# OMODRI_EtherCAT_0.net
KiCad netlist of a schematic drawn in Altium Designer
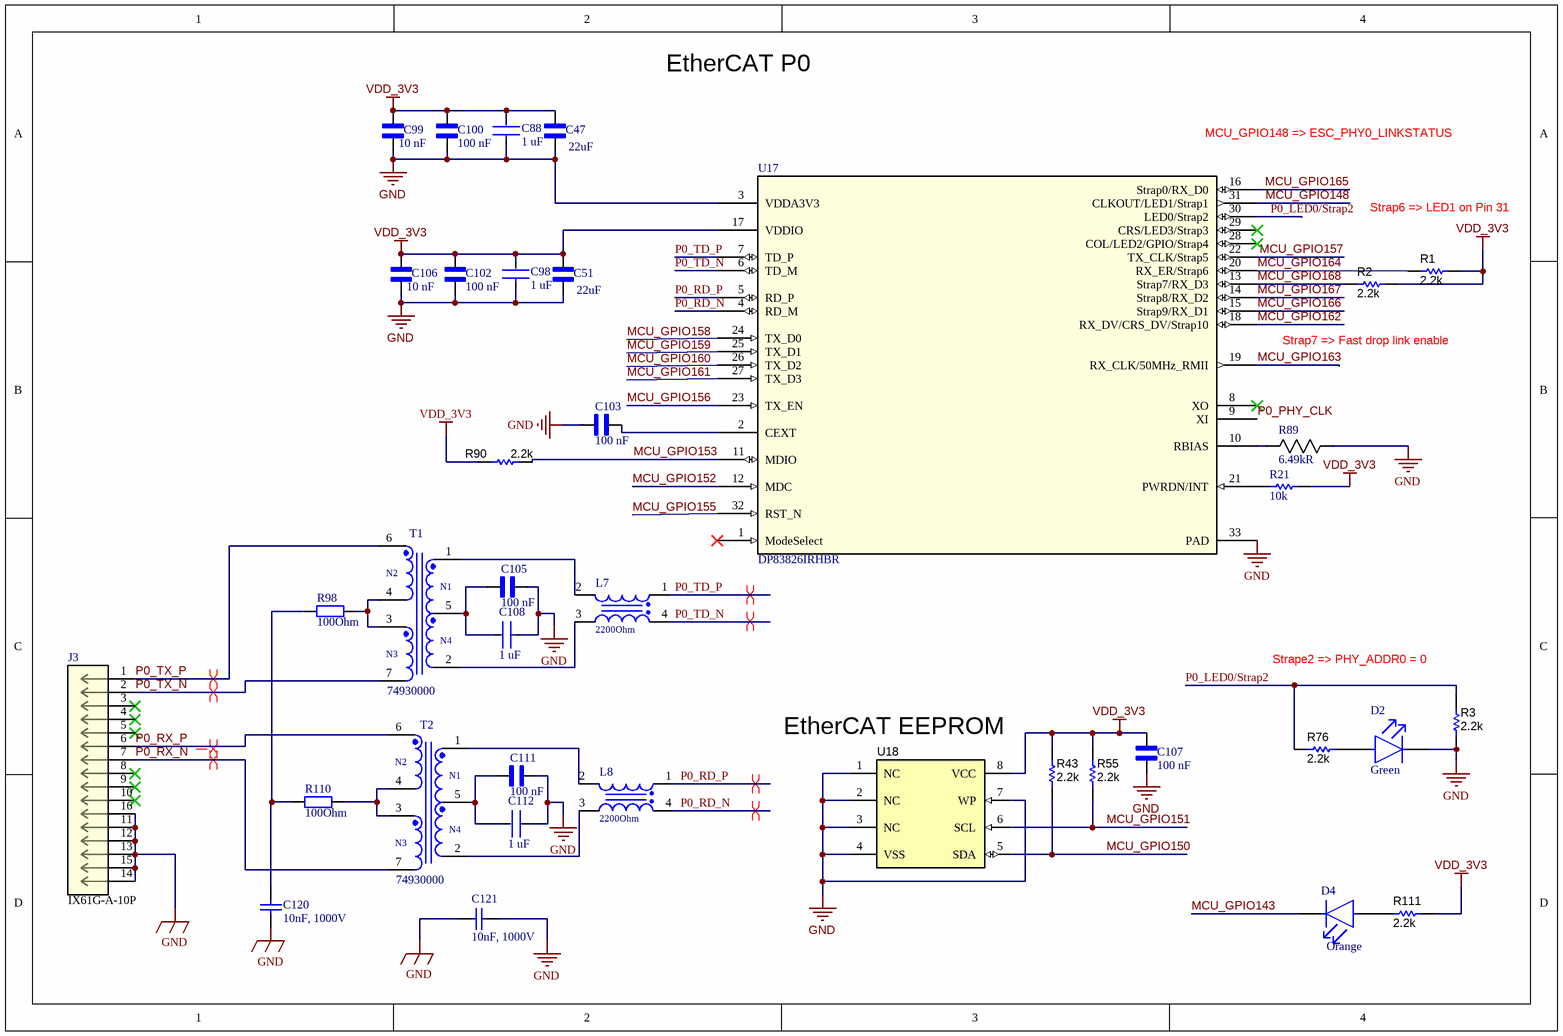
[diagram p0: OMODRI_EtherCAT_0.SchDoc]

(export (version "E")
  (design (tool "Eeschema 10.0.6"))
  (components
    (comp (ref "C47")
      (value "22uF")
      (footprint "CAPC1005X55N")
      (description "22µF ±20% 6.3V Ceramic Capacitor X5R 0402 (1005 Metric)")
      (fields (field (name "MP") "CL05A226MQ5N6J8") (field (name "MF") "Samsung Electro-Mechanics"))
      (libsource (lib "CL05A226MQ5N6J8") (part "CL05A226MQ5N6J8"))
    )
    (comp (ref "C51")
      (value "22uF")
      (footprint "CAPC1005X55N")
      (description "22µF ±20% 6.3V Ceramic Capacitor X5R 0402 (1005 Metric)")
      (fields (field (name "MP") "CL05A226MQ5N6J8") (field (name "MF") "Samsung Electro-Mechanics"))
      (libsource (lib "CL05A226MQ5N6J8") (part "CL05A226MQ5N6J8"))
    )
    (comp (ref "C88")
      (value "1 uF")
      (footprint "FP-CC0201-BA-MFG")
      (description "CAP CER 1UF 6.3V X5R 0201")
      (fields (field (name "TOLERANCE") "0.2") (field (name "MANUFACTURER") "Yageo"))
      (libsource (lib "Altium Content Vault") (part "11868f565c42a9108669ba33697ecf6"))
    )
    (comp (ref "C98")
      (value "1 uF")
      (footprint "FP-CC0201-BA-MFG")
      (description "CAP CER 1UF 6.3V X5R 0201")
      (fields (field (name "TOLERANCE") "0.2") (field (name "MANUFACTURER") "Yageo"))
      (libsource (lib "Altium Content Vault") (part "11868f565c42a9108669ba33697ecf6"))
    )
    (comp (ref "C99")
      (value "10 nF")
      (footprint "CAPC0603X33N")
      (description "SMD Capacitor X7R_EIA_ with Capacitance: 10000pF Tol. 10%. Rated Voltage: 25Vdc")
      (fields (field (name "MP") "GRM033R71E103KE14D") (field (name "MF") "Murata"))
      (libsource (lib "GRM033R71E103KE14D") (part "GRM033R71E103KE14D"))
    )
    (comp (ref "C100")
      (value "100 nF")
      (footprint "CAPC0603X33N")
      (description "SMD Capacitor X5R_EIA_ with Capacitance: 0.10uF Tol. 10%. Rated Voltage: 25Vdc")
      (fields (field (name "MF") "Murata") (field (name "MP") "GRM033R61E104KE14D"))
      (libsource (lib "") (part "GRM033R61E104KE14D_2"))
    )
    (comp (ref "C102")
      (value "100 nF")
      (footprint "CAPC0603X33N")
      (description "SMD Capacitor X5R_EIA_ with Capacitance: 0.10uF Tol. 10%. Rated Voltage: 25Vdc")
      (fields (field (name "MF") "Murata") (field (name "MP") "GRM033R61E104KE14D"))
      (libsource (lib "") (part "GRM033R61E104KE14D_2"))
    )
    (comp (ref "C103")
      (value "100 nF")
      (footprint "CAPC0603X33N")
      (description "SMD Capacitor X5R_EIA_ with Capacitance: 0.10uF Tol. 10%. Rated Voltage: 25Vdc")
      (fields (field (name "MF") "Murata") (field (name "MP") "GRM033R61E104KE14D"))
      (libsource (lib "") (part "GRM033R61E104KE14D_1"))
    )
    (comp (ref "C105")
      (value "100 nF")
      (footprint "CAPC0603X33N")
      (description "SMD Capacitor X5R_EIA_ with Capacitance: 0.10uF Tol. 10%. Rated Voltage: 25Vdc")
      (fields (field (name "MF") "Murata") (field (name "MP") "GRM033R61E104KE14D"))
      (libsource (lib "") (part "GRM033R61E104KE14D_1"))
    )
    (comp (ref "C106")
      (value "10 nF")
      (footprint "CAPC0603X33N")
      (description "SMD Capacitor X7R_EIA_ with Capacitance: 10000pF Tol. 10%. Rated Voltage: 25Vdc")
      (fields (field (name "MP") "GRM033R71E103KE14D") (field (name "MF") "Murata"))
      (libsource (lib "GRM033R71E103KE14D") (part "GRM033R71E103KE14D"))
    )
    (comp (ref "C107")
      (value "100 nF")
      (footprint "CAPC0603X33N")
      (description "SMD Capacitor X5R_EIA_ with Capacitance: 0.10uF Tol. 10%. Rated Voltage: 25Vdc")
      (fields (field (name "MF") "Murata") (field (name "MP") "GRM033R61E104KE14D"))
      (libsource (lib "GRM033R61E104KE14D") (part "GRM033R61E104KE14D"))
    )
    (comp (ref "C108")
      (value "1 uF")
      (footprint "FP-CC0201-BA-MFG")
      (description "CAP CER 1UF 6.3V X5R 0201")
      (fields (field (name "TOLERANCE") "0.2") (field (name "MANUFACTURER") "Yageo"))
      (libsource (lib "Altium Content Vault") (part "11868f565c42a9108669ba33697ecf6"))
    )
    (comp (ref "C111")
      (value "100 nF")
      (footprint "CAPC0603X33N")
      (description "SMD Capacitor X5R_EIA_ with Capacitance: 0.10uF Tol. 10%. Rated Voltage: 25Vdc")
      (fields (field (name "MF") "Murata") (field (name "MP") "GRM033R61E104KE14D"))
      (libsource (lib "") (part "GRM033R61E104KE14D_1"))
    )
    (comp (ref "C112")
      (value "1 uF")
      (footprint "FP-CC0201-BA-MFG")
      (description "CAP CER 1UF 6.3V X5R 0201")
      (fields (field (name "TOLERANCE") "0.2") (field (name "MANUFACTURER") "Yageo"))
      (libsource (lib "Altium Content Vault") (part "11868f565c42a9108669ba33697ecf6"))
    )
    (comp (ref "C120")
      (value "10nF, 1000V")
      (footprint "WCAP-CSMH_1206_H=1.25mm")
      (description "WCAP-CSMH Ceramic Capacitors, size 1206, 10nF, 1000VDC")
      (fields (field (name "PART NUMBER") "885342208021") (field (name "PUBLISHER") "Wurth Elektronik"))
      (libsource (lib "WCAP-CSMH_1206") (part "885342208021"))
    )
    (comp (ref "C121")
      (value "10nF, 1000V")
      (footprint "WCAP-CSMH_1206_H=1.25mm")
      (description "WCAP-CSMH Ceramic Capacitors, size 1206, 10nF, 1000VDC")
      (fields (field (name "PART NUMBER") "885342208021") (field (name "PUBLISHER") "Wurth Elektronik"))
      (libsource (lib "WCAP-CSMH_1206") (part "885342208021"))
    )
    (comp (ref "D2")
      (value "SML-P11MTT86R")
      (footprint "ROHM-SML-P11MT_V")
      (description "LED Uni-Color Yellow Green 2-Pin Chip 0402(1006Metric) T/R")
      (fields
        (field (name "MANUFACTURER") "Rohm")
        (field (name "MANUFACTURER PART NUMBER") "SML-P11MTT86")
        (field (name "ILLUMINATION COLOR") "Green")
      )
      (libsource (lib "LED") (part "SML-P11MTT86R"))
    )
    (comp (ref "D4")
      (value "SML-P11DTT86R")
      (footprint "ROHM-SML-P11MT_V")
      (description "LED ORANGE CLEAR 1006 SMD")
      (fields (field (name "MANUFACTURER") "Rohm") (field (name "COLOR") "Orange"))
      (libsource (lib "LED") (part "SML-P11DTT86R"))
    )
    (comp (ref "J3")
      (value "Part Number: IX61G-A-10P")
      (footprint "CONN_1G-A-10P")
      (description "Conn Ethernet Connector RCP 10 POS Solder RA Thru-Hole 10 Terminal 1 Port Cat 5e/Cat 6a Reel")
      (fields
        (field (name "MANUFACTURER_PART_NUMBER") "IX61G-A-10P")
        (field (name "MANUFACTURER") "Hirose")
        (field (name "MANUFACTURER PART NUMBER") "IX61G-A-10P")
        (field (name "COPYRIGHT") "Copyright (C) 2018 Accelerated Designs. All rights reserved")
      )
      (libsource (lib "Hirose-iX") (part "IX61G-A-10P"))
    )
    (comp (ref "L7")
      (value "2200Ohm")
      (footprint "WE-CNSW_1206")
      (description "WE-CNSW SMT Common Mode Line Filter, size 1206, 2200Ohm, 0.2A, 50V")
      (fields
        (field (name "MANUFACTURER PART NUMBER") "744232222")
        (field (name "MANUFACTURER") "Wurth Elektronik")
      )
      (libsource (lib "WE-CNSW_1206") (part "744232222"))
    )
    (comp (ref "L8")
      (value "2200Ohm")
      (footprint "WE-CNSW_1206")
      (description "WE-CNSW SMT Common Mode Line Filter, size 1206, 2200Ohm, 0.2A, 50V")
      (fields
        (field (name "MANUFACTURER PART NUMBER") "744232222")
        (field (name "MANUFACTURER") "Wurth Elektronik")
      )
      (libsource (lib "WE-CNSW_1206") (part "744232222"))
    )
    (comp (ref "R1")
      (value "CRCW04022K20JNED")
      (footprint "0402")
      (description "RES, 2.2 k, 5%, 0.063 W, AEC-Q200 Grade 0, 0402")
      (fields (field (name "MANUFACTURER") "Vishay-Dale") (field (name "VALUEDISPLAYED") "2.2k"))
      (libsource (lib "Altium Vault - TI") (part "Resistor"))
    )
    (comp (ref "R2")
      (value "CRCW04022K20JNED")
      (footprint "0402")
      (description "RES, 2.2 k, 5%, 0.063 W, AEC-Q200 Grade 0, 0402")
      (fields (field (name "MANUFACTURER") "Vishay-Dale") (field (name "VALUEDISPLAYED") "2.2k"))
      (libsource (lib "Altium Vault - TI") (part "Resistor"))
    )
    (comp (ref "R3")
      (value "CRCW04022K20JNED")
      (footprint "0402")
      (description "RES, 2.2 k, 5%, 0.063 W, AEC-Q200 Grade 0, 0402")
      (fields (field (name "MANUFACTURER") "Vishay-Dale") (field (name "VALUEDISPLAYED") "2.2k"))
      (libsource (lib "Altium Vault - TI") (part "Resistor"))
    )
    (comp (ref "R21")
      (value "ERJ2RKF1002X")
      (footprint "RESC1005X40X25LL05T05")
      (description "Chip Resistor, 10 KOhm, +/- 1%, 0.1 W, -55 to 155 degC, 0402 (1005 Metric), RoHS, Tape and Reel")
      (fields
        (field (name "RESISTANCE") "10k")
        (field (name "TOLERANCE") "1%")
        (field (name "MANUFACTURER") "Panasonic")
      )
      (libsource (lib "Altium Content Vault") (part "RES-2"))
    )
    (comp (ref "R43")
      (value "CRCW04022K20JNED")
      (footprint "0402")
      (description "RES, 2.2 k, 5%, 0.063 W, AEC-Q200 Grade 0, 0402")
      (fields (field (name "MANUFACTURER") "Vishay-Dale") (field (name "VALUEDISPLAYED") "2.2k"))
      (libsource (lib "Altium Vault - TI") (part "Resistor"))
    )
    (comp (ref "R55")
      (value "CRCW04022K20JNED")
      (footprint "0402")
      (description "RES, 2.2 k, 5%, 0.063 W, AEC-Q200 Grade 0, 0402")
      (fields (field (name "MANUFACTURER") "Vishay-Dale") (field (name "VALUEDISPLAYED") "2.2k"))
      (libsource (lib "Altium Vault - TI") (part "Resistor"))
    )
    (comp (ref "R76")
      (value "CRCW04022K20JNED")
      (footprint "0402")
      (description "RES, 2.2 k, 5%, 0.063 W, AEC-Q200 Grade 0, 0402")
      (fields (field (name "MANUFACTURER") "Vishay-Dale") (field (name "VALUEDISPLAYED") "2.2k"))
      (libsource (lib "Altium Vault - TI") (part "Resistor"))
    )
    (comp (ref "R89")
      (value "Part Number: CRCW04026K49FKED")
      (footprint "RES_CRCW_0402")
      (description "Res Thick Film 0402 6.49K Ohm 1% 0.063W(1/16W) ±100ppm/C Pad SMD Automotive T/R")
      (fields
        (field (name "MANUFACTURER_PART_NUMBER") "CRCW04026K49FKED")
        (field (name "MANUFACTURER") "Vishay")
        (field (name "RESISTANCE") "6.49kR")
        (field (name "COPYRIGHT") "Copyright (C) 2018 Accelerated Designs. All rights reserved")
      )
      (libsource (lib "Vishay-Resistor") (part "CRCW04026K49FKED"))
    )
    (comp (ref "R90")
      (value "CRCW04022K20JNED")
      (footprint "0402")
      (description "RES, 2.2 k, 5%, 0.063 W, AEC-Q200 Grade 0, 0402")
      (fields (field (name "MANUFACTURER") "Vishay-Dale") (field (name "VALUEDISPLAYED") "2.2k"))
      (libsource (lib "Altium Vault - TI") (part "Resistor"))
    )
    (comp (ref "R98")
      (value "100Ohm")
      (footprint "WRIS-KWKB_0612_H=0.55mm")
      (description "WRIS-KWKB Thick Film Resistors, size 0612, 100Ohm, +/-5%, 0.75W")
      (fields (field (name "PART NUMBER") "561020132009") (field (name "PUBLISHER") "Wurth Elektronik"))
      (libsource (lib "561020132009_Altium_WRIS-KWKB_rev19a") (part "561020132009"))
    )
    (comp (ref "R110")
      (value "100Ohm")
      (footprint "WRIS-KWKB_0612_H=0.55mm")
      (description "WRIS-KWKB Thick Film Resistors, size 0612, 100Ohm, +/-5%, 0.75W")
      (fields (field (name "PART NUMBER") "561020132009") (field (name "PUBLISHER") "Wurth Elektronik"))
      (libsource (lib "561020132009_Altium_WRIS-KWKB_rev19a") (part "561020132009"))
    )
    (comp (ref "R111")
      (value "CRCW04022K20JNED")
      (footprint "0402")
      (description "RES, 2.2 k, 5%, 0.063 W, AEC-Q200 Grade 0, 0402")
      (fields (field (name "MANUFACTURER") "Vishay-Dale") (field (name "VALUEDISPLAYED") "2.2k"))
      (libsource (lib "Altium Vault - TI") (part "Resistor"))
    )
    (comp (ref "T1")
      (value "74930000")
      (footprint "74930000")
      (description "WE-STST Super Tiny Signal Transformer, size 4532, 350uH")
      (fields (field (name "PUBLISHER") "Wurth Elektronik"))
      (libsource (lib "WE-STST") (part "74930000"))
    )
    (comp (ref "T2")
      (value "74930000")
      (footprint "74930000")
      (description "WE-STST Super Tiny Signal Transformer, size 4532, 350uH")
      (fields (field (name "PUBLISHER") "Wurth Elektronik"))
      (libsource (lib "WE-STST") (part "74930000"))
    )
    (comp (ref "U17")
      (value "DP83826IRHBR")
      (footprint "RHB0032B")
      (fields (field (name "MANUFACTURER") "Texas Instruments"))
      (libsource (lib "TI-DP8382x") (part "DP83826IRHBR"))
    )
    (comp (ref "U18")
      (value "CAT24C16WI-GT3")
      (footprint "SOIC-8")
      (description "16 Kb I2C EEPROM Serial, SOIC-8")
      (fields (field (name "MANUFACTURER") "ON Semiconductor"))
      (libsource (lib "Altium Vault - TI") (part "EEPROM_8P_1-3NC"))
    )
  )
  (nets
    (net (code "1") (name "/MCU_GPIO143") (class "Default")
      (node (ref "D4") (pin "1") (pinfunction "C_1") (pintype "passive"))
    )
    (net (code "2") (name "/MCU_GPIO148") (class "Default")
      (node (ref "U17") (pin "31") (pinfunction "CLKOUT/LED1/Strap1_31") (pintype "output"))
    )
    (net (code "3") (name "/MCU_GPIO150") (class "Default")
      (node (ref "R43") (pin "2") (pinfunction "2_2") (pintype "passive"))
      (node (ref "U18") (pin "5") (pinfunction "SDA_5") (pintype "bidirectional"))
    )
    (net (code "4") (name "/MCU_GPIO151") (class "Default")
      (node (ref "R55") (pin "2") (pinfunction "2_2") (pintype "passive"))
      (node (ref "U18") (pin "6") (pinfunction "SCL_6") (pintype "input"))
    )
    (net (code "5") (name "/MCU_GPIO152") (class "Default")
      (node (ref "U17") (pin "12") (pinfunction "MDC_12") (pintype "input"))
    )
    (net (code "6") (name "/MCU_GPIO153") (class "Default")
      (node (ref "R90") (pin "1") (pinfunction "1_1") (pintype "passive"))
      (node (ref "U17") (pin "11") (pinfunction "MDIO_11") (pintype "bidirectional"))
    )
    (net (code "7") (name "/MCU_GPIO155") (class "Default")
      (node (ref "U17") (pin "32") (pinfunction "RST_N_32") (pintype "input"))
    )
    (net (code "8") (name "/MCU_GPIO156") (class "Default")
      (node (ref "U17") (pin "23") (pinfunction "TX_EN_23") (pintype "input"))
    )
    (net (code "9") (name "/MCU_GPIO157") (class "Default")
      (node (ref "U17") (pin "22") (pinfunction "TX_CLK/Strap5_22") (pintype "bidirectional"))
    )
    (net (code "10") (name "/MCU_GPIO158") (class "Default")
      (node (ref "U17") (pin "24") (pinfunction "TX_D0_24") (pintype "input"))
    )
    (net (code "11") (name "/MCU_GPIO159") (class "Default")
      (node (ref "U17") (pin "25") (pinfunction "TX_D1_25") (pintype "input"))
    )
    (net (code "12") (name "/MCU_GPIO160") (class "Default")
      (node (ref "U17") (pin "26") (pinfunction "TX_D2_26") (pintype "input"))
    )
    (net (code "13") (name "/MCU_GPIO161") (class "Default")
      (node (ref "U17") (pin "27") (pinfunction "TX_D3_27") (pintype "input"))
    )
    (net (code "14") (name "/MCU_GPIO162") (class "Default")
      (node (ref "U17") (pin "18") (pinfunction "RX_DV/CRS_DV/Strap10_18") (pintype "bidirectional"))
    )
    (net (code "15") (name "/MCU_GPIO163") (class "Default")
      (node (ref "U17") (pin "19") (pinfunction "RX_CLK/50MHz_RMII_19") (pintype "output"))
    )
    (net (code "16") (name "/MCU_GPIO164") (class "Default")
      (node (ref "R1") (pin "2") (pinfunction "2_2") (pintype "passive"))
      (node (ref "U17") (pin "20") (pinfunction "RX_ER/Strap6_20") (pintype "bidirectional"))
    )
    (net (code "17") (name "/MCU_GPIO165") (class "Default")
      (node (ref "U17") (pin "16") (pinfunction "Strap0/RX_D0_16") (pintype "bidirectional"))
    )
    (net (code "18") (name "/MCU_GPIO166") (class "Default")
      (node (ref "U17") (pin "15") (pinfunction "Strap9/RX_D1_15") (pintype "bidirectional"))
    )
    (net (code "19") (name "/MCU_GPIO167") (class "Default")
      (node (ref "U17") (pin "14") (pinfunction "Strap8/RX_D2_14") (pintype "bidirectional"))
    )
    (net (code "20") (name "/MCU_GPIO168") (class "Default")
      (node (ref "R2") (pin "2") (pinfunction "2_2") (pintype "passive"))
      (node (ref "U17") (pin "13") (pinfunction "Strap7/RX_D3_13") (pintype "bidirectional"))
    )
    (net (code "21") (name "/P0_LED0{slash}Strap2") (class "Default")
      (node (ref "R3") (pin "1") (pinfunction "1_1") (pintype "passive"))
      (node (ref "R76") (pin "2") (pinfunction "2_2") (pintype "passive"))
      (node (ref "U17") (pin "30") (pinfunction "LED0/Strap2_30") (pintype "bidirectional"))
    )
    (net (code "22") (name "/P0_PHY_CLK") (class "Default")
      (node (ref "U17") (pin "9") (pinfunction "XI_9") (pintype "passive"))
    )
    (net (code "23") (name "/P0_RD_N") (class "Default")
      (node (ref "L8") (pin "4") (pinfunction "4_4") (pintype "passive"))
      (node (ref "U17") (pin "4") (pinfunction "RD_M_4") (pintype "bidirectional"))
    )
    (net (code "24") (name "/P0_RD_P") (class "Default")
      (node (ref "L8") (pin "1") (pinfunction "1_1") (pintype "passive"))
      (node (ref "U17") (pin "5") (pinfunction "RD_P_5") (pintype "bidirectional"))
    )
    (net (code "25") (name "/P0_RX_N") (class "Default")
      (node (ref "J3") (pin "7") (pinfunction "7_7") (pintype "passive"))
      (node (ref "T2") (pin "7") (pinfunction "7_7") (pintype "passive"))
    )
    (net (code "26") (name "/P0_RX_P") (class "Default")
      (node (ref "J3") (pin "6") (pinfunction "6_6") (pintype "passive"))
      (node (ref "T2") (pin "6") (pinfunction "6_6") (pintype "passive"))
    )
    (net (code "27") (name "/P0_TD_N") (class "Default")
      (node (ref "L7") (pin "4") (pinfunction "4_4") (pintype "passive"))
      (node (ref "U17") (pin "6") (pinfunction "TD_M_6") (pintype "bidirectional"))
    )
    (net (code "28") (name "/P0_TD_P") (class "Default")
      (node (ref "L7") (pin "1") (pinfunction "1_1") (pintype "passive"))
      (node (ref "U17") (pin "7") (pinfunction "TD_P_7") (pintype "bidirectional"))
    )
    (net (code "29") (name "/P0_TX_N") (class "Default")
      (node (ref "J3") (pin "2") (pinfunction "2_2") (pintype "passive"))
      (node (ref "T1") (pin "7") (pinfunction "7_7") (pintype "passive"))
    )
    (net (code "30") (name "/P0_TX_P") (class "Default")
      (node (ref "J3") (pin "1") (pinfunction "1_1") (pintype "passive"))
      (node (ref "T1") (pin "6") (pinfunction "6_6") (pintype "passive"))
    )
    (net (code "31") (name "GND") (class "Default")
      (node (ref "C100") (pin "1") (pinfunction "1_1") (pintype "passive"))
      (node (ref "C102") (pin "1") (pinfunction "1_1") (pintype "passive"))
      (node (ref "C103") (pin "2") (pinfunction "2_2") (pintype "passive"))
      (node (ref "C105") (pin "1") (pinfunction "1_1") (pintype "passive"))
      (node (ref "C106") (pin "1") (pinfunction "1_1") (pintype "passive"))
      (node (ref "C107") (pin "2") (pinfunction "2_2") (pintype "passive"))
      (node (ref "C108") (pin "1") (pinfunction "1_1") (pintype "passive"))
      (node (ref "C111") (pin "1") (pinfunction "1_1") (pintype "passive"))
      (node (ref "C112") (pin "1") (pinfunction "1_1") (pintype "passive"))
      (node (ref "C120") (pin "1") (pinfunction "1_1") (pintype "passive"))
      (node (ref "C121") (pin "1") (pinfunction "1_1") (pintype "passive"))
      (node (ref "C121") (pin "2") (pinfunction "2_2") (pintype "passive"))
      (node (ref "C47") (pin "1") (pinfunction "1_1") (pintype "passive"))
      (node (ref "C51") (pin "1") (pinfunction "1_1") (pintype "passive"))
      (node (ref "C88") (pin "1") (pinfunction "1_1") (pintype "passive"))
      (node (ref "C98") (pin "1") (pinfunction "1_1") (pintype "passive"))
      (node (ref "C99") (pin "1") (pinfunction "1_1") (pintype "passive"))
      (node (ref "D2") (pin "1") (pinfunction "C_1") (pintype "passive"))
      (node (ref "J3") (pin "11") (pinfunction "11_11") (pintype "passive"))
      (node (ref "J3") (pin "12") (pinfunction "12_12") (pintype "passive"))
      (node (ref "J3") (pin "13") (pinfunction "13_13") (pintype "passive"))
      (node (ref "J3") (pin "14") (pinfunction "14_14") (pintype "passive"))
      (node (ref "J3") (pin "15") (pinfunction "15_15") (pintype "passive"))
      (node (ref "J3") (pin "16") (pinfunction "16_16") (pintype "passive"))
      (node (ref "R3") (pin "2") (pinfunction "2_2") (pintype "passive"))
      (node (ref "R89") (pin "1") (pinfunction "1_1") (pintype "passive"))
      (node (ref "U17") (pin "3") (pinfunction "VDDA3V3_3") (pintype "power_in"))
      (node (ref "U17") (pin "33") (pinfunction "PAD_33") (pintype "power_in"))
      (node (ref "U18") (pin "1") (pinfunction "NC_1") (pintype "passive"))
      (node (ref "U18") (pin "2") (pinfunction "NC_2") (pintype "passive"))
      (node (ref "U18") (pin "3") (pinfunction "NC_3") (pintype "passive"))
      (node (ref "U18") (pin "4") (pinfunction "VSS_4") (pintype "power_in"))
      (node (ref "U18") (pin "7") (pinfunction "WP_7") (pintype "input"))
    )
    (net (code "32") (name "Net-(C105-Pad2)") (class "Default")
      (node (ref "C105") (pin "2") (pinfunction "2_2") (pintype "passive"))
      (node (ref "C108") (pin "2") (pinfunction "2_2") (pintype "passive"))
      (node (ref "T1") (pin "5") (pinfunction "5_5") (pintype "passive"))
    )
    (net (code "33") (name "Net-(C111-Pad2)") (class "Default")
      (node (ref "C111") (pin "2") (pinfunction "2_2") (pintype "passive"))
      (node (ref "C112") (pin "2") (pinfunction "2_2") (pintype "passive"))
      (node (ref "T2") (pin "5") (pinfunction "5_5") (pintype "passive"))
    )
    (net (code "34") (name "Net-(C120-Pad2)") (class "Default")
      (node (ref "C120") (pin "2") (pinfunction "2_2") (pintype "passive"))
      (node (ref "R110") (pin "1") (pinfunction "1_1") (pintype "passive"))
      (node (ref "R98") (pin "1") (pinfunction "1_1") (pintype "passive"))
    )
    (net (code "35") (name "Net-(D2-A)") (class "Default")
      (node (ref "D2") (pin "2") (pinfunction "A_2") (pintype "passive"))
      (node (ref "R76") (pin "1") (pinfunction "1_1") (pintype "passive"))
    )
    (net (code "36") (name "Net-(D4-A)") (class "Default")
      (node (ref "D4") (pin "2") (pinfunction "A_2") (pintype "passive"))
      (node (ref "R111") (pin "2") (pinfunction "2_2") (pintype "passive"))
    )
    (net (code "37") (name "Net-(L7-Pad2)") (class "Default")
      (node (ref "L7") (pin "2") (pinfunction "2_2") (pintype "passive"))
      (node (ref "T1") (pin "1") (pinfunction "1_1") (pintype "passive"))
    )
    (net (code "38") (name "Net-(L7-Pad3)") (class "Default")
      (node (ref "L7") (pin "3") (pinfunction "3_3") (pintype "passive"))
      (node (ref "T1") (pin "2") (pinfunction "2_2") (pintype "passive"))
    )
    (net (code "39") (name "Net-(L8-Pad2)") (class "Default")
      (node (ref "L8") (pin "2") (pinfunction "2_2") (pintype "passive"))
      (node (ref "T2") (pin "1") (pinfunction "1_1") (pintype "passive"))
    )
    (net (code "40") (name "Net-(L8-Pad3)") (class "Default")
      (node (ref "L8") (pin "3") (pinfunction "3_3") (pintype "passive"))
      (node (ref "T2") (pin "2") (pinfunction "2_2") (pintype "passive"))
    )
    (net (code "41") (name "Net-(R98-Pad2)") (class "Default")
      (node (ref "R98") (pin "2") (pinfunction "2_2") (pintype "passive"))
      (node (ref "T1") (pin "3") (pinfunction "3_3") (pintype "passive"))
      (node (ref "T1") (pin "4") (pinfunction "4_4") (pintype "passive"))
    )
    (net (code "42") (name "Net-(R110-Pad2)") (class "Default")
      (node (ref "R110") (pin "2") (pinfunction "2_2") (pintype "passive"))
      (node (ref "T2") (pin "3") (pinfunction "3_3") (pintype "passive"))
      (node (ref "T2") (pin "4") (pinfunction "4_4") (pintype "passive"))
    )
    (net (code "43") (name "Net-(U17-CEXT)") (class "Default")
      (node (ref "C103") (pin "1") (pinfunction "1_1") (pintype "passive"))
      (node (ref "U17") (pin "2") (pinfunction "CEXT_2") (pintype "passive"))
    )
    (net (code "44") (name "Net-(U17-PWRDN{slash}INT)") (class "Default")
      (node (ref "R21") (pin "2") (pinfunction "2_2") (pintype "passive"))
      (node (ref "U17") (pin "21") (pinfunction "PWRDN/INT_21") (pintype "input"))
    )
    (net (code "45") (name "Net-(U17-RBIAS)") (class "Default")
      (node (ref "R89") (pin "2") (pinfunction "2_2") (pintype "passive"))
      (node (ref "U17") (pin "10") (pinfunction "RBIAS_10") (pintype "passive"))
    )
    (net (code "46") (name "VDD_3V3") (class "Default")
      (node (ref "C100") (pin "2") (pinfunction "2_2") (pintype "passive"))
      (node (ref "C102") (pin "2") (pinfunction "2_2") (pintype "passive"))
      (node (ref "C106") (pin "2") (pinfunction "2_2") (pintype "passive"))
      (node (ref "C107") (pin "1") (pinfunction "1_1") (pintype "passive"))
      (node (ref "C47") (pin "2") (pinfunction "2_2") (pintype "passive"))
      (node (ref "C51") (pin "2") (pinfunction "2_2") (pintype "passive"))
      (node (ref "C88") (pin "2") (pinfunction "2_2") (pintype "passive"))
      (node (ref "C98") (pin "2") (pinfunction "2_2") (pintype "passive"))
      (node (ref "C99") (pin "2") (pinfunction "2_2") (pintype "passive"))
      (node (ref "R1") (pin "1") (pinfunction "1_1") (pintype "passive"))
      (node (ref "R111") (pin "1") (pinfunction "1_1") (pintype "passive"))
      (node (ref "R2") (pin "1") (pinfunction "1_1") (pintype "passive"))
      (node (ref "R21") (pin "1") (pinfunction "1_1") (pintype "passive"))
      (node (ref "R43") (pin "1") (pinfunction "1_1") (pintype "passive"))
      (node (ref "R55") (pin "1") (pinfunction "1_1") (pintype "passive"))
      (node (ref "R90") (pin "2") (pinfunction "2_2") (pintype "passive"))
      (node (ref "U17") (pin "17") (pinfunction "VDDIO_17") (pintype "power_in"))
      (node (ref "U18") (pin "8") (pinfunction "VCC_8") (pintype "power_in"))
    )
    (net (code "47") (name "unconnected-(J3-Pad3)") (class "Default")
      (node (ref "J3") (pin "3") (pinfunction "3_3") (pintype "passive+no_connect"))
    )
    (net (code "48") (name "unconnected-(J3-Pad4)") (class "Default")
      (node (ref "J3") (pin "4") (pinfunction "4_4") (pintype "passive+no_connect"))
    )
    (net (code "49") (name "unconnected-(J3-Pad5)") (class "Default")
      (node (ref "J3") (pin "5") (pinfunction "5_5") (pintype "passive+no_connect"))
    )
    (net (code "50") (name "unconnected-(J3-Pad8)") (class "Default")
      (node (ref "J3") (pin "8") (pinfunction "8_8") (pintype "passive+no_connect"))
    )
    (net (code "51") (name "unconnected-(J3-Pad9)") (class "Default")
      (node (ref "J3") (pin "9") (pinfunction "9_9") (pintype "passive+no_connect"))
    )
    (net (code "52") (name "unconnected-(J3-Pad10)") (class "Default")
      (node (ref "J3") (pin "10") (pinfunction "10_10") (pintype "passive+no_connect"))
    )
    (net (code "53") (name "unconnected-(U17-COL{slash}LED2{slash}GPIO{slash}Strap4-Pad28)") (class "Default")
      (node (ref "U17") (pin "28") (pinfunction "COL/LED2/GPIO/Strap4_28") (pintype "bidirectional+no_connect"))
    )
    (net (code "54") (name "unconnected-(U17-CRS{slash}LED3{slash}Strap3-Pad29)") (class "Default")
      (node (ref "U17") (pin "29") (pinfunction "CRS/LED3/Strap3_29") (pintype "bidirectional+no_connect"))
    )
    (net (code "55") (name "unconnected-(U17-ModeSelect-Pad1)") (class "Default")
      (node (ref "U17") (pin "1") (pinfunction "ModeSelect_1") (pintype "input+no_connect"))
    )
    (net (code "56") (name "unconnected-(U17-XO-Pad8)") (class "Default")
      (node (ref "U17") (pin "8") (pinfunction "XO_8") (pintype "passive+no_connect"))
    )
  )
)
